# base_led_cube.net
KiCad netlist of a schematic drawn in Altium Designer
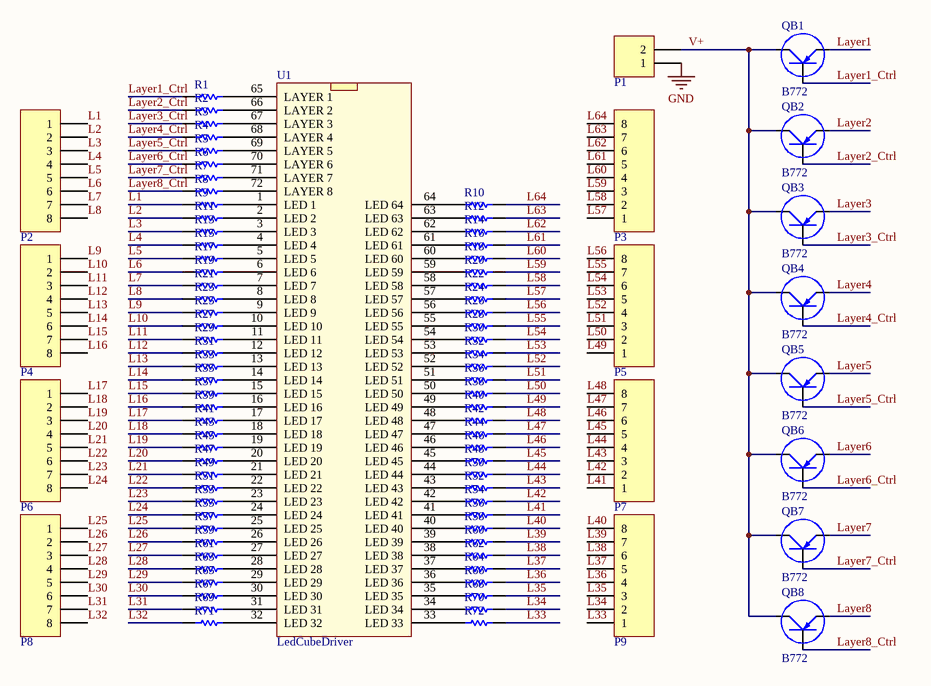
[diagram p0: base_led_cube.SchDoc]

(export (version "E")
  (design (tool "Eeschema 10.0.6"))
  (components
    (comp (ref "P1")
      (value "Domino 2")
      (footprint "DOMINO SMALL 2")
      (description "Domino, 2-Pin")
      (fields (field (name "PUBLISHER") "Altium Limited"))
      (libsource (lib "PIF_Library") (part "Domino 2"))
    )
    (comp (ref "P2")
      (value "Header 8")
      (footprint "JP8")
      (description "Header, 8-Pin")
      (fields (field (name "PUBLISHER") "Altium Limited"))
      (libsource (lib "") (part "Header 8_1"))
    )
    (comp (ref "P3")
      (value "Header 8")
      (footprint "JP8")
      (description "Header, 8-Pin")
      (fields (field (name "PUBLISHER") "Altium Limited"))
      (libsource (lib "PIF_Library") (part "Header 8"))
    )
    (comp (ref "P4")
      (value "Header 8")
      (footprint "JP8")
      (description "Header, 8-Pin")
      (fields (field (name "PUBLISHER") "Altium Limited"))
      (libsource (lib "") (part "Header 8_1"))
    )
    (comp (ref "P5")
      (value "Header 8")
      (footprint "JP8")
      (description "Header, 8-Pin")
      (fields (field (name "PUBLISHER") "Altium Limited"))
      (libsource (lib "PIF_Library") (part "Header 8"))
    )
    (comp (ref "P6")
      (value "Header 8")
      (footprint "JP8")
      (description "Header, 8-Pin")
      (fields (field (name "PUBLISHER") "Altium Limited"))
      (libsource (lib "") (part "Header 8_1"))
    )
    (comp (ref "P7")
      (value "Header 8")
      (footprint "JP8")
      (description "Header, 8-Pin")
      (fields (field (name "PUBLISHER") "Altium Limited"))
      (libsource (lib "PIF_Library") (part "Header 8"))
    )
    (comp (ref "P8")
      (value "Header 8")
      (footprint "JP8")
      (description "Header, 8-Pin")
      (fields (field (name "PUBLISHER") "Altium Limited"))
      (libsource (lib "") (part "Header 8_1"))
    )
    (comp (ref "P9")
      (value "Header 8")
      (footprint "JP8")
      (description "Header, 8-Pin")
      (fields (field (name "PUBLISHER") "Altium Limited"))
      (libsource (lib "PIF_Library") (part "Header 8"))
    )
    (comp (ref "QB1")
      (value "B772")
      (footprint "To-126")
      (description "PNP 30V - 3A")
      (libsource (lib "HN_Library") (part "2SB772"))
    )
    (comp (ref "QB2")
      (value "B772")
      (footprint "To-126")
      (description "PNP 30V - 3A")
      (libsource (lib "HN_Library") (part "2SB772"))
    )
    (comp (ref "QB3")
      (value "B772")
      (footprint "To-126")
      (description "PNP 30V - 3A")
      (libsource (lib "HN_Library") (part "2SB772"))
    )
    (comp (ref "QB4")
      (value "B772")
      (footprint "To-126")
      (description "PNP 30V - 3A")
      (libsource (lib "HN_Library") (part "2SB772"))
    )
    (comp (ref "QB5")
      (value "B772")
      (footprint "To-126")
      (description "PNP 30V - 3A")
      (libsource (lib "HN_Library") (part "2SB772"))
    )
    (comp (ref "QB6")
      (value "B772")
      (footprint "To-126")
      (description "PNP 30V - 3A")
      (libsource (lib "HN_Library") (part "2SB772"))
    )
    (comp (ref "QB7")
      (value "B772")
      (footprint "To-126")
      (description "PNP 30V - 3A")
      (libsource (lib "HN_Library") (part "2SB772"))
    )
    (comp (ref "QB8")
      (value "B772")
      (footprint "To-126")
      (description "PNP 30V - 3A")
      (libsource (lib "HN_Library") (part "2SB772"))
    )
    (comp (ref "R1")
      (value "RESISTOR SMD")
      (footprint "RES-SM-0805")
      (description "Resistor")
      (libsource (lib "PIF_Library") (part "RESISTOR SMD"))
    )
    (comp (ref "R2")
      (value "RESISTOR SMD")
      (footprint "RES-SM-0805")
      (description "Resistor")
      (libsource (lib "PIF_Library") (part "RESISTOR SMD"))
    )
    (comp (ref "R3")
      (value "RESISTOR SMD")
      (footprint "RES-SM-0805")
      (description "Resistor")
      (libsource (lib "PIF_Library") (part "RESISTOR SMD"))
    )
    (comp (ref "R4")
      (value "RESISTOR SMD")
      (footprint "RES-SM-0805")
      (description "Resistor")
      (libsource (lib "PIF_Library") (part "RESISTOR SMD"))
    )
    (comp (ref "R5")
      (value "RESISTOR SMD")
      (footprint "RES-SM-0805")
      (description "Resistor")
      (libsource (lib "PIF_Library") (part "RESISTOR SMD"))
    )
    (comp (ref "R6")
      (value "RESISTOR SMD")
      (footprint "RES-SM-0805")
      (description "Resistor")
      (libsource (lib "PIF_Library") (part "RESISTOR SMD"))
    )
    (comp (ref "R7")
      (value "RESISTOR SMD")
      (footprint "RES-SM-0805")
      (description "Resistor")
      (libsource (lib "PIF_Library") (part "RESISTOR SMD"))
    )
    (comp (ref "R8")
      (value "RESISTOR SMD")
      (footprint "RES-SM-0805")
      (description "Resistor")
      (libsource (lib "PIF_Library") (part "RESISTOR SMD"))
    )
    (comp (ref "R9")
      (value "RESISTOR SMD")
      (footprint "RES-SM-0805")
      (description "Resistor")
      (libsource (lib "PIF_Library") (part "RESISTOR SMD"))
    )
    (comp (ref "R10")
      (value "RESISTOR SMD")
      (footprint "RES-SM-0805")
      (description "Resistor")
      (libsource (lib "PIF_Library") (part "RESISTOR SMD"))
    )
    (comp (ref "R11")
      (value "RESISTOR SMD")
      (footprint "RES-SM-0805")
      (description "Resistor")
      (libsource (lib "PIF_Library") (part "RESISTOR SMD"))
    )
    (comp (ref "R12")
      (value "RESISTOR SMD")
      (footprint "RES-SM-0805")
      (description "Resistor")
      (libsource (lib "PIF_Library") (part "RESISTOR SMD"))
    )
    (comp (ref "R13")
      (value "RESISTOR SMD")
      (footprint "RES-SM-0805")
      (description "Resistor")
      (libsource (lib "PIF_Library") (part "RESISTOR SMD"))
    )
    (comp (ref "R14")
      (value "RESISTOR SMD")
      (footprint "RES-SM-0805")
      (description "Resistor")
      (libsource (lib "PIF_Library") (part "RESISTOR SMD"))
    )
    (comp (ref "R15")
      (value "RESISTOR SMD")
      (footprint "RES-SM-0805")
      (description "Resistor")
      (libsource (lib "PIF_Library") (part "RESISTOR SMD"))
    )
    (comp (ref "R16")
      (value "RESISTOR SMD")
      (footprint "RES-SM-0805")
      (description "Resistor")
      (libsource (lib "PIF_Library") (part "RESISTOR SMD"))
    )
    (comp (ref "R17")
      (value "RESISTOR SMD")
      (footprint "RES-SM-0805")
      (description "Resistor")
      (libsource (lib "PIF_Library") (part "RESISTOR SMD"))
    )
    (comp (ref "R18")
      (value "RESISTOR SMD")
      (footprint "RES-SM-0805")
      (description "Resistor")
      (libsource (lib "PIF_Library") (part "RESISTOR SMD"))
    )
    (comp (ref "R19")
      (value "RESISTOR SMD")
      (footprint "RES-SM-0805")
      (description "Resistor")
      (libsource (lib "PIF_Library") (part "RESISTOR SMD"))
    )
    (comp (ref "R20")
      (value "RESISTOR SMD")
      (footprint "RES-SM-0805")
      (description "Resistor")
      (libsource (lib "PIF_Library") (part "RESISTOR SMD"))
    )
    (comp (ref "R21")
      (value "RESISTOR SMD")
      (footprint "RES-SM-0805")
      (description "Resistor")
      (libsource (lib "PIF_Library") (part "RESISTOR SMD"))
    )
    (comp (ref "R22")
      (value "RESISTOR SMD")
      (footprint "RES-SM-0805")
      (description "Resistor")
      (libsource (lib "PIF_Library") (part "RESISTOR SMD"))
    )
    (comp (ref "R23")
      (value "RESISTOR SMD")
      (footprint "RES-SM-0805")
      (description "Resistor")
      (libsource (lib "PIF_Library") (part "RESISTOR SMD"))
    )
    (comp (ref "R24")
      (value "RESISTOR SMD")
      (footprint "RES-SM-0805")
      (description "Resistor")
      (libsource (lib "PIF_Library") (part "RESISTOR SMD"))
    )
    (comp (ref "R25")
      (value "RESISTOR SMD")
      (footprint "RES-SM-0805")
      (description "Resistor")
      (libsource (lib "PIF_Library") (part "RESISTOR SMD"))
    )
    (comp (ref "R26")
      (value "RESISTOR SMD")
      (footprint "RES-SM-0805")
      (description "Resistor")
      (libsource (lib "PIF_Library") (part "RESISTOR SMD"))
    )
    (comp (ref "R27")
      (value "RESISTOR SMD")
      (footprint "RES-SM-0805")
      (description "Resistor")
      (libsource (lib "PIF_Library") (part "RESISTOR SMD"))
    )
    (comp (ref "R28")
      (value "RESISTOR SMD")
      (footprint "RES-SM-0805")
      (description "Resistor")
      (libsource (lib "PIF_Library") (part "RESISTOR SMD"))
    )
    (comp (ref "R29")
      (value "RESISTOR SMD")
      (footprint "RES-SM-0805")
      (description "Resistor")
      (libsource (lib "PIF_Library") (part "RESISTOR SMD"))
    )
    (comp (ref "R30")
      (value "RESISTOR SMD")
      (footprint "RES-SM-0805")
      (description "Resistor")
      (libsource (lib "PIF_Library") (part "RESISTOR SMD"))
    )
    (comp (ref "R31")
      (value "RESISTOR SMD")
      (footprint "RES-SM-0805")
      (description "Resistor")
      (libsource (lib "PIF_Library") (part "RESISTOR SMD"))
    )
    (comp (ref "R32")
      (value "RESISTOR SMD")
      (footprint "RES-SM-0805")
      (description "Resistor")
      (libsource (lib "PIF_Library") (part "RESISTOR SMD"))
    )
    (comp (ref "R33")
      (value "RESISTOR SMD")
      (footprint "RES-SM-0805")
      (description "Resistor")
      (libsource (lib "PIF_Library") (part "RESISTOR SMD"))
    )
    (comp (ref "R34")
      (value "RESISTOR SMD")
      (footprint "RES-SM-0805")
      (description "Resistor")
      (libsource (lib "PIF_Library") (part "RESISTOR SMD"))
    )
    (comp (ref "R35")
      (value "RESISTOR SMD")
      (footprint "RES-SM-0805")
      (description "Resistor")
      (libsource (lib "PIF_Library") (part "RESISTOR SMD"))
    )
    (comp (ref "R36")
      (value "RESISTOR SMD")
      (footprint "RES-SM-0805")
      (description "Resistor")
      (libsource (lib "PIF_Library") (part "RESISTOR SMD"))
    )
    (comp (ref "R37")
      (value "RESISTOR SMD")
      (footprint "RES-SM-0805")
      (description "Resistor")
      (libsource (lib "PIF_Library") (part "RESISTOR SMD"))
    )
    (comp (ref "R38")
      (value "RESISTOR SMD")
      (footprint "RES-SM-0805")
      (description "Resistor")
      (libsource (lib "PIF_Library") (part "RESISTOR SMD"))
    )
    (comp (ref "R39")
      (value "RESISTOR SMD")
      (footprint "RES-SM-0805")
      (description "Resistor")
      (libsource (lib "PIF_Library") (part "RESISTOR SMD"))
    )
    (comp (ref "R40")
      (value "RESISTOR SMD")
      (footprint "RES-SM-0805")
      (description "Resistor")
      (libsource (lib "PIF_Library") (part "RESISTOR SMD"))
    )
    (comp (ref "R41")
      (value "RESISTOR SMD")
      (footprint "RES-SM-0805")
      (description "Resistor")
      (libsource (lib "PIF_Library") (part "RESISTOR SMD"))
    )
    (comp (ref "R42")
      (value "RESISTOR SMD")
      (footprint "RES-SM-0805")
      (description "Resistor")
      (libsource (lib "PIF_Library") (part "RESISTOR SMD"))
    )
    (comp (ref "R43")
      (value "RESISTOR SMD")
      (footprint "RES-SM-0805")
      (description "Resistor")
      (libsource (lib "PIF_Library") (part "RESISTOR SMD"))
    )
    (comp (ref "R44")
      (value "RESISTOR SMD")
      (footprint "RES-SM-0805")
      (description "Resistor")
      (libsource (lib "PIF_Library") (part "RESISTOR SMD"))
    )
    (comp (ref "R45")
      (value "RESISTOR SMD")
      (footprint "RES-SM-0805")
      (description "Resistor")
      (libsource (lib "PIF_Library") (part "RESISTOR SMD"))
    )
    (comp (ref "R46")
      (value "RESISTOR SMD")
      (footprint "RES-SM-0805")
      (description "Resistor")
      (libsource (lib "PIF_Library") (part "RESISTOR SMD"))
    )
    (comp (ref "R47")
      (value "RESISTOR SMD")
      (footprint "RES-SM-0805")
      (description "Resistor")
      (libsource (lib "PIF_Library") (part "RESISTOR SMD"))
    )
    (comp (ref "R48")
      (value "RESISTOR SMD")
      (footprint "RES-SM-0805")
      (description "Resistor")
      (libsource (lib "PIF_Library") (part "RESISTOR SMD"))
    )
    (comp (ref "R49")
      (value "RESISTOR SMD")
      (footprint "RES-SM-0805")
      (description "Resistor")
      (libsource (lib "PIF_Library") (part "RESISTOR SMD"))
    )
    (comp (ref "R50")
      (value "RESISTOR SMD")
      (footprint "RES-SM-0805")
      (description "Resistor")
      (libsource (lib "PIF_Library") (part "RESISTOR SMD"))
    )
    (comp (ref "R51")
      (value "RESISTOR SMD")
      (footprint "RES-SM-0805")
      (description "Resistor")
      (libsource (lib "PIF_Library") (part "RESISTOR SMD"))
    )
    (comp (ref "R52")
      (value "RESISTOR SMD")
      (footprint "RES-SM-0805")
      (description "Resistor")
      (libsource (lib "PIF_Library") (part "RESISTOR SMD"))
    )
    (comp (ref "R53")
      (value "RESISTOR SMD")
      (footprint "RES-SM-0805")
      (description "Resistor")
      (libsource (lib "PIF_Library") (part "RESISTOR SMD"))
    )
    (comp (ref "R54")
      (value "RESISTOR SMD")
      (footprint "RES-SM-0805")
      (description "Resistor")
      (libsource (lib "PIF_Library") (part "RESISTOR SMD"))
    )
    (comp (ref "R55")
      (value "RESISTOR SMD")
      (footprint "RES-SM-0805")
      (description "Resistor")
      (libsource (lib "PIF_Library") (part "RESISTOR SMD"))
    )
    (comp (ref "R56")
      (value "RESISTOR SMD")
      (footprint "RES-SM-0805")
      (description "Resistor")
      (libsource (lib "PIF_Library") (part "RESISTOR SMD"))
    )
    (comp (ref "R57")
      (value "RESISTOR SMD")
      (footprint "RES-SM-0805")
      (description "Resistor")
      (libsource (lib "PIF_Library") (part "RESISTOR SMD"))
    )
    (comp (ref "R58")
      (value "RESISTOR SMD")
      (footprint "RES-SM-0805")
      (description "Resistor")
      (libsource (lib "PIF_Library") (part "RESISTOR SMD"))
    )
    (comp (ref "R59")
      (value "RESISTOR SMD")
      (footprint "RES-SM-0805")
      (description "Resistor")
      (libsource (lib "PIF_Library") (part "RESISTOR SMD"))
    )
    (comp (ref "R60")
      (value "RESISTOR SMD")
      (footprint "RES-SM-0805")
      (description "Resistor")
      (libsource (lib "PIF_Library") (part "RESISTOR SMD"))
    )
    (comp (ref "R61")
      (value "RESISTOR SMD")
      (footprint "RES-SM-0805")
      (description "Resistor")
      (libsource (lib "PIF_Library") (part "RESISTOR SMD"))
    )
    (comp (ref "R62")
      (value "RESISTOR SMD")
      (footprint "RES-SM-0805")
      (description "Resistor")
      (libsource (lib "PIF_Library") (part "RESISTOR SMD"))
    )
    (comp (ref "R63")
      (value "RESISTOR SMD")
      (footprint "RES-SM-0805")
      (description "Resistor")
      (libsource (lib "PIF_Library") (part "RESISTOR SMD"))
    )
    (comp (ref "R64")
      (value "RESISTOR SMD")
      (footprint "RES-SM-0805")
      (description "Resistor")
      (libsource (lib "PIF_Library") (part "RESISTOR SMD"))
    )
    (comp (ref "R65")
      (value "RESISTOR SMD")
      (footprint "RES-SM-0805")
      (description "Resistor")
      (libsource (lib "PIF_Library") (part "RESISTOR SMD"))
    )
    (comp (ref "R66")
      (value "RESISTOR SMD")
      (footprint "RES-SM-0805")
      (description "Resistor")
      (libsource (lib "PIF_Library") (part "RESISTOR SMD"))
    )
    (comp (ref "R67")
      (value "RESISTOR SMD")
      (footprint "RES-SM-0805")
      (description "Resistor")
      (libsource (lib "PIF_Library") (part "RESISTOR SMD"))
    )
    (comp (ref "R68")
      (value "RESISTOR SMD")
      (footprint "RES-SM-0805")
      (description "Resistor")
      (libsource (lib "PIF_Library") (part "RESISTOR SMD"))
    )
    (comp (ref "R69")
      (value "RESISTOR SMD")
      (footprint "RES-SM-0805")
      (description "Resistor")
      (libsource (lib "PIF_Library") (part "RESISTOR SMD"))
    )
    (comp (ref "R70")
      (value "RESISTOR SMD")
      (footprint "RES-SM-0805")
      (description "Resistor")
      (libsource (lib "PIF_Library") (part "RESISTOR SMD"))
    )
    (comp (ref "R71")
      (value "RESISTOR SMD")
      (footprint "RES-SM-0805")
      (description "Resistor")
      (libsource (lib "PIF_Library") (part "RESISTOR SMD"))
    )
    (comp (ref "R72")
      (value "RESISTOR SMD")
      (footprint "RES-SM-0805")
      (description "Resistor")
      (libsource (lib "PIF_Library") (part "RESISTOR SMD"))
    )
    (comp (ref "U1")
      (value "LedCubeDriver")
      (footprint "LED CUBE Driver")
      (libsource (lib "HN_Library") (part "LED Cube Driver"))
    )
  )
  (nets
    (net (code "1") (name "/L1") (class "Default")
      (node (ref "P2") (pin "1") (pinfunction "1_1") (pintype "passive"))
      (node (ref "R9") (pin "1") (pinfunction "1_1") (pintype "passive"))
    )
    (net (code "2") (name "/L2") (class "Default")
      (node (ref "P2") (pin "2") (pinfunction "2_2") (pintype "passive"))
      (node (ref "R11") (pin "1") (pinfunction "1_1") (pintype "passive"))
    )
    (net (code "3") (name "/L3") (class "Default")
      (node (ref "P2") (pin "3") (pinfunction "3_3") (pintype "passive"))
      (node (ref "R13") (pin "1") (pinfunction "1_1") (pintype "passive"))
    )
    (net (code "4") (name "/L4") (class "Default")
      (node (ref "P2") (pin "4") (pinfunction "4_4") (pintype "passive"))
      (node (ref "R15") (pin "1") (pinfunction "1_1") (pintype "passive"))
    )
    (net (code "5") (name "/L5") (class "Default")
      (node (ref "P2") (pin "5") (pinfunction "5_5") (pintype "passive"))
      (node (ref "R17") (pin "1") (pinfunction "1_1") (pintype "passive"))
    )
    (net (code "6") (name "/L6") (class "Default")
      (node (ref "P2") (pin "6") (pinfunction "6_6") (pintype "passive"))
      (node (ref "R19") (pin "1") (pinfunction "1_1") (pintype "passive"))
    )
    (net (code "7") (name "/L7") (class "Default")
      (node (ref "P2") (pin "7") (pinfunction "7_7") (pintype "passive"))
      (node (ref "R21") (pin "1") (pinfunction "1_1") (pintype "passive"))
    )
    (net (code "8") (name "/L8") (class "Default")
      (node (ref "P2") (pin "8") (pinfunction "8_8") (pintype "passive"))
      (node (ref "R23") (pin "1") (pinfunction "1_1") (pintype "passive"))
    )
    (net (code "9") (name "/L9") (class "Default")
      (node (ref "P4") (pin "1") (pinfunction "1_1") (pintype "passive"))
      (node (ref "R25") (pin "1") (pinfunction "1_1") (pintype "passive"))
    )
    (net (code "10") (name "/L10") (class "Default")
      (node (ref "P4") (pin "2") (pinfunction "2_2") (pintype "passive"))
      (node (ref "R27") (pin "1") (pinfunction "1_1") (pintype "passive"))
    )
    (net (code "11") (name "/L11") (class "Default")
      (node (ref "P4") (pin "3") (pinfunction "3_3") (pintype "passive"))
      (node (ref "R29") (pin "1") (pinfunction "1_1") (pintype "passive"))
    )
    (net (code "12") (name "/L12") (class "Default")
      (node (ref "P4") (pin "4") (pinfunction "4_4") (pintype "passive"))
      (node (ref "R31") (pin "1") (pinfunction "1_1") (pintype "passive"))
    )
    (net (code "13") (name "/L13") (class "Default")
      (node (ref "P4") (pin "5") (pinfunction "5_5") (pintype "passive"))
      (node (ref "R33") (pin "1") (pinfunction "1_1") (pintype "passive"))
    )
    (net (code "14") (name "/L14") (class "Default")
      (node (ref "P4") (pin "6") (pinfunction "6_6") (pintype "passive"))
      (node (ref "R35") (pin "1") (pinfunction "1_1") (pintype "passive"))
    )
    (net (code "15") (name "/L15") (class "Default")
      (node (ref "P4") (pin "7") (pinfunction "7_7") (pintype "passive"))
      (node (ref "R37") (pin "1") (pinfunction "1_1") (pintype "passive"))
    )
    (net (code "16") (name "/L16") (class "Default")
      (node (ref "P4") (pin "8") (pinfunction "8_8") (pintype "passive"))
      (node (ref "R39") (pin "1") (pinfunction "1_1") (pintype "passive"))
    )
    (net (code "17") (name "/L17") (class "Default")
      (node (ref "P6") (pin "1") (pinfunction "1_1") (pintype "passive"))
      (node (ref "R41") (pin "1") (pinfunction "1_1") (pintype "passive"))
    )
    (net (code "18") (name "/L18") (class "Default")
      (node (ref "P6") (pin "2") (pinfunction "2_2") (pintype "passive"))
      (node (ref "R43") (pin "1") (pinfunction "1_1") (pintype "passive"))
    )
    (net (code "19") (name "/L19") (class "Default")
      (node (ref "P6") (pin "3") (pinfunction "3_3") (pintype "passive"))
      (node (ref "R45") (pin "1") (pinfunction "1_1") (pintype "passive"))
    )
    (net (code "20") (name "/L20") (class "Default")
      (node (ref "P6") (pin "4") (pinfunction "4_4") (pintype "passive"))
      (node (ref "R47") (pin "1") (pinfunction "1_1") (pintype "passive"))
    )
    (net (code "21") (name "/L21") (class "Default")
      (node (ref "P6") (pin "5") (pinfunction "5_5") (pintype "passive"))
      (node (ref "R49") (pin "1") (pinfunction "1_1") (pintype "passive"))
    )
    (net (code "22") (name "/L22") (class "Default")
      (node (ref "P6") (pin "6") (pinfunction "6_6") (pintype "passive"))
      (node (ref "R51") (pin "1") (pinfunction "1_1") (pintype "passive"))
    )
    (net (code "23") (name "/L23") (class "Default")
      (node (ref "P6") (pin "7") (pinfunction "7_7") (pintype "passive"))
      (node (ref "R53") (pin "1") (pinfunction "1_1") (pintype "passive"))
    )
    (net (code "24") (name "/L24") (class "Default")
      (node (ref "P6") (pin "8") (pinfunction "8_8") (pintype "passive"))
      (node (ref "R55") (pin "1") (pinfunction "1_1") (pintype "passive"))
    )
    (net (code "25") (name "/L25") (class "Default")
      (node (ref "P8") (pin "1") (pinfunction "1_1") (pintype "passive"))
      (node (ref "R57") (pin "1") (pinfunction "1_1") (pintype "passive"))
    )
    (net (code "26") (name "/L26") (class "Default")
      (node (ref "P8") (pin "2") (pinfunction "2_2") (pintype "passive"))
      (node (ref "R59") (pin "1") (pinfunction "1_1") (pintype "passive"))
    )
    (net (code "27") (name "/L27") (class "Default")
      (node (ref "P8") (pin "3") (pinfunction "3_3") (pintype "passive"))
      (node (ref "R61") (pin "1") (pinfunction "1_1") (pintype "passive"))
    )
    (net (code "28") (name "/L28") (class "Default")
      (node (ref "P8") (pin "4") (pinfunction "4_4") (pintype "passive"))
      (node (ref "R63") (pin "1") (pinfunction "1_1") (pintype "passive"))
    )
    (net (code "29") (name "/L29") (class "Default")
      (node (ref "P8") (pin "5") (pinfunction "5_5") (pintype "passive"))
      (node (ref "R65") (pin "1") (pinfunction "1_1") (pintype "passive"))
    )
    (net (code "30") (name "/L30") (class "Default")
      (node (ref "P8") (pin "6") (pinfunction "6_6") (pintype "passive"))
      (node (ref "R67") (pin "1") (pinfunction "1_1") (pintype "passive"))
    )
    (net (code "31") (name "/L31") (class "Default")
      (node (ref "P8") (pin "7") (pinfunction "7_7") (pintype "passive"))
      (node (ref "R69") (pin "1") (pinfunction "1_1") (pintype "passive"))
    )
    (net (code "32") (name "/L32") (class "Default")
      (node (ref "P8") (pin "8") (pinfunction "8_8") (pintype "passive"))
      (node (ref "R71") (pin "1") (pinfunction "1_1") (pintype "passive"))
    )
    (net (code "33") (name "/L33") (class "Default")
      (node (ref "P9") (pin "1") (pinfunction "1_1") (pintype "passive"))
      (node (ref "R72") (pin "1") (pinfunction "1_1") (pintype "passive"))
    )
    (net (code "34") (name "/L34") (class "Default")
      (node (ref "P9") (pin "2") (pinfunction "2_2") (pintype "passive"))
      (node (ref "R70") (pin "1") (pinfunction "1_1") (pintype "passive"))
    )
    (net (code "35") (name "/L35") (class "Default")
      (node (ref "P9") (pin "3") (pinfunction "3_3") (pintype "passive"))
      (node (ref "R68") (pin "1") (pinfunction "1_1") (pintype "passive"))
    )
    (net (code "36") (name "/L36") (class "Default")
      (node (ref "P9") (pin "4") (pinfunction "4_4") (pintype "passive"))
      (node (ref "R66") (pin "1") (pinfunction "1_1") (pintype "passive"))
    )
    (net (code "37") (name "/L37") (class "Default")
      (node (ref "P9") (pin "5") (pinfunction "5_5") (pintype "passive"))
      (node (ref "R64") (pin "1") (pinfunction "1_1") (pintype "passive"))
    )
    (net (code "38") (name "/L38") (class "Default")
      (node (ref "P9") (pin "6") (pinfunction "6_6") (pintype "passive"))
      (node (ref "R62") (pin "1") (pinfunction "1_1") (pintype "passive"))
    )
    (net (code "39") (name "/L39") (class "Default")
      (node (ref "P9") (pin "7") (pinfunction "7_7") (pintype "passive"))
      (node (ref "R60") (pin "1") (pinfunction "1_1") (pintype "passive"))
    )
    (net (code "40") (name "/L40") (class "Default")
      (node (ref "P9") (pin "8") (pinfunction "8_8") (pintype "passive"))
      (node (ref "R58") (pin "1") (pinfunction "1_1") (pintype "passive"))
    )
    (net (code "41") (name "/L41") (class "Default")
      (node (ref "P7") (pin "1") (pinfunction "1_1") (pintype "passive"))
      (node (ref "R56") (pin "1") (pinfunction "1_1") (pintype "passive"))
    )
    (net (code "42") (name "/L42") (class "Default")
      (node (ref "P7") (pin "2") (pinfunction "2_2") (pintype "passive"))
      (node (ref "R54") (pin "1") (pinfunction "1_1") (pintype "passive"))
    )
    (net (code "43") (name "/L43") (class "Default")
      (node (ref "P7") (pin "3") (pinfunction "3_3") (pintype "passive"))
      (node (ref "R52") (pin "1") (pinfunction "1_1") (pintype "passive"))
    )
    (net (code "44") (name "/L44") (class "Default")
      (node (ref "P7") (pin "4") (pinfunction "4_4") (pintype "passive"))
      (node (ref "R50") (pin "1") (pinfunction "1_1") (pintype "passive"))
    )
    (net (code "45") (name "/L45") (class "Default")
      (node (ref "P7") (pin "5") (pinfunction "5_5") (pintype "passive"))
      (node (ref "R48") (pin "1") (pinfunction "1_1") (pintype "passive"))
    )
    (net (code "46") (name "/L46") (class "Default")
      (node (ref "P7") (pin "6") (pinfunction "6_6") (pintype "passive"))
      (node (ref "R46") (pin "1") (pinfunction "1_1") (pintype "passive"))
    )
    (net (code "47") (name "/L47") (class "Default")
      (node (ref "P7") (pin "7") (pinfunction "7_7") (pintype "passive"))
      (node (ref "R44") (pin "1") (pinfunction "1_1") (pintype "passive"))
    )
    (net (code "48") (name "/L48") (class "Default")
      (node (ref "P7") (pin "8") (pinfunction "8_8") (pintype "passive"))
      (node (ref "R42") (pin "1") (pinfunction "1_1") (pintype "passive"))
    )
    (net (code "49") (name "/L49") (class "Default")
      (node (ref "P5") (pin "1") (pinfunction "1_1") (pintype "passive"))
      (node (ref "R40") (pin "1") (pinfunction "1_1") (pintype "passive"))
    )
    (net (code "50") (name "/L50") (class "Default")
      (node (ref "P5") (pin "2") (pinfunction "2_2") (pintype "passive"))
      (node (ref "R38") (pin "1") (pinfunction "1_1") (pintype "passive"))
    )
    (net (code "51") (name "/L51") (class "Default")
      (node (ref "P5") (pin "3") (pinfunction "3_3") (pintype "passive"))
      (node (ref "R36") (pin "1") (pinfunction "1_1") (pintype "passive"))
    )
    (net (code "52") (name "/L52") (class "Default")
      (node (ref "P5") (pin "4") (pinfunction "4_4") (pintype "passive"))
      (node (ref "R34") (pin "1") (pinfunction "1_1") (pintype "passive"))
    )
    (net (code "53") (name "/L53") (class "Default")
      (node (ref "P5") (pin "5") (pinfunction "5_5") (pintype "passive"))
      (node (ref "R32") (pin "1") (pinfunction "1_1") (pintype "passive"))
    )
    (net (code "54") (name "/L54") (class "Default")
      (node (ref "P5") (pin "6") (pinfunction "6_6") (pintype "passive"))
      (node (ref "R30") (pin "1") (pinfunction "1_1") (pintype "passive"))
    )
    (net (code "55") (name "/L55") (class "Default")
      (node (ref "P5") (pin "7") (pinfunction "7_7") (pintype "passive"))
      (node (ref "R28") (pin "1") (pinfunction "1_1") (pintype "passive"))
    )
    (net (code "56") (name "/L56") (class "Default")
      (node (ref "P5") (pin "8") (pinfunction "8_8") (pintype "passive"))
      (node (ref "R26") (pin "1") (pinfunction "1_1") (pintype "passive"))
    )
    (net (code "57") (name "/L57") (class "Default")
      (node (ref "P3") (pin "1") (pinfunction "1_1") (pintype "passive"))
      (node (ref "R24") (pin "1") (pinfunction "1_1") (pintype "passive"))
    )
    (net (code "58") (name "/L58") (class "Default")
      (node (ref "P3") (pin "2") (pinfunction "2_2") (pintype "passive"))
      (node (ref "R22") (pin "1") (pinfunction "1_1") (pintype "passive"))
    )
    (net (code "59") (name "/L59") (class "Default")
      (node (ref "P3") (pin "3") (pinfunction "3_3") (pintype "passive"))
      (node (ref "R20") (pin "1") (pinfunction "1_1") (pintype "passive"))
    )
    (net (code "60") (name "/L60") (class "Default")
      (node (ref "P3") (pin "4") (pinfunction "4_4") (pintype "passive"))
      (node (ref "R18") (pin "1") (pinfunction "1_1") (pintype "passive"))
    )
    (net (code "61") (name "/L61") (class "Default")
      (node (ref "P3") (pin "5") (pinfunction "5_5") (pintype "passive"))
      (node (ref "R16") (pin "1") (pinfunction "1_1") (pintype "passive"))
    )
    (net (code "62") (name "/L62") (class "Default")
      (node (ref "P3") (pin "6") (pinfunction "6_6") (pintype "passive"))
      (node (ref "R14") (pin "1") (pinfunction "1_1") (pintype "passive"))
    )
    (net (code "63") (name "/L63") (class "Default")
      (node (ref "P3") (pin "7") (pinfunction "7_7") (pintype "passive"))
      (node (ref "R12") (pin "1") (pinfunction "1_1") (pintype "passive"))
    )
    (net (code "64") (name "/L64") (class "Default")
      (node (ref "P3") (pin "8") (pinfunction "8_8") (pintype "passive"))
      (node (ref "R10") (pin "1") (pinfunction "1_1") (pintype "passive"))
    )
    (net (code "65") (name "/Layer1") (class "Default")
      (node (ref "QB1") (pin "3") (pinfunction "E_3") (pintype "passive"))
    )
    (net (code "66") (name "/Layer1_Ctrl") (class "Default")
      (node (ref "QB1") (pin "1") (pinfunction "B_1") (pintype "passive"))
      (node (ref "R1") (pin "1") (pinfunction "1_1") (pintype "passive"))
    )
    (net (code "67") (name "/Layer2") (class "Default")
      (node (ref "QB2") (pin "3") (pinfunction "E_3") (pintype "passive"))
    )
    (net (code "68") (name "/Layer2_Ctrl") (class "Default")
      (node (ref "QB2") (pin "1") (pinfunction "B_1") (pintype "passive"))
      (node (ref "R2") (pin "1") (pinfunction "1_1") (pintype "passive"))
    )
    (net (code "69") (name "/Layer3") (class "Default")
      (node (ref "QB3") (pin "3") (pinfunction "E_3") (pintype "passive"))
    )
    (net (code "70") (name "/Layer3_Ctrl") (class "Default")
      (node (ref "QB3") (pin "1") (pinfunction "B_1") (pintype "passive"))
      (node (ref "R3") (pin "1") (pinfunction "1_1") (pintype "passive"))
    )
    (net (code "71") (name "/Layer4") (class "Default")
      (node (ref "QB4") (pin "3") (pinfunction "E_3") (pintype "passive"))
    )
    (net (code "72") (name "/Layer4_Ctrl") (class "Default")
      (node (ref "QB4") (pin "1") (pinfunction "B_1") (pintype "passive"))
      (node (ref "R4") (pin "1") (pinfunction "1_1") (pintype "passive"))
    )
    (net (code "73") (name "/Layer5") (class "Default")
      (node (ref "QB5") (pin "3") (pinfunction "E_3") (pintype "passive"))
    )
    (net (code "74") (name "/Layer5_Ctrl") (class "Default")
      (node (ref "QB5") (pin "1") (pinfunction "B_1") (pintype "passive"))
      (node (ref "R5") (pin "1") (pinfunction "1_1") (pintype "passive"))
    )
    (net (code "75") (name "/Layer6") (class "Default")
      (node (ref "QB6") (pin "3") (pinfunction "E_3") (pintype "passive"))
    )
    (net (code "76") (name "/Layer6_Ctrl") (class "Default")
      (node (ref "QB6") (pin "1") (pinfunction "B_1") (pintype "passive"))
      (node (ref "R6") (pin "1") (pinfunction "1_1") (pintype "passive"))
    )
    (net (code "77") (name "/Layer7") (class "Default")
      (node (ref "QB7") (pin "3") (pinfunction "E_3") (pintype "passive"))
    )
    (net (code "78") (name "/Layer7_Ctrl") (class "Default")
      (node (ref "QB7") (pin "1") (pinfunction "B_1") (pintype "passive"))
      (node (ref "R7") (pin "1") (pinfunction "1_1") (pintype "passive"))
    )
    (net (code "79") (name "/Layer8") (class "Default")
      (node (ref "QB8") (pin "3") (pinfunction "E_3") (pintype "passive"))
    )
    (net (code "80") (name "/Layer8_Ctrl") (class "Default")
      (node (ref "QB8") (pin "1") (pinfunction "B_1") (pintype "passive"))
      (node (ref "R8") (pin "1") (pinfunction "1_1") (pintype "passive"))
    )
    (net (code "81") (name "/V+") (class "Default")
      (node (ref "P1") (pin "2") (pinfunction "2_2") (pintype "passive"))
      (node (ref "QB1") (pin "2") (pinfunction "C_2") (pintype "passive"))
      (node (ref "QB2") (pin "2") (pinfunction "C_2") (pintype "passive"))
      (node (ref "QB3") (pin "2") (pinfunction "C_2") (pintype "passive"))
      (node (ref "QB4") (pin "2") (pinfunction "C_2") (pintype "passive"))
      (node (ref "QB5") (pin "2") (pinfunction "C_2") (pintype "passive"))
      (node (ref "QB6") (pin "2") (pinfunction "C_2") (pintype "passive"))
      (node (ref "QB7") (pin "2") (pinfunction "C_2") (pintype "passive"))
      (node (ref "QB8") (pin "2") (pinfunction "C_2") (pintype "passive"))
    )
    (net (code "82") (name "GND") (class "Default")
      (node (ref "P1") (pin "1") (pinfunction "1_1") (pintype "passive"))
    )
    (net (code "83") (name "Net-(U1-LAYER_1)") (class "Default")
      (node (ref "R1") (pin "2") (pinfunction "2_2") (pintype "passive"))
      (node (ref "U1") (pin "65") (pinfunction "LAYER_1_65") (pintype "passive"))
    )
    (net (code "84") (name "Net-(U1-LAYER_2)") (class "Default")
      (node (ref "R2") (pin "2") (pinfunction "2_2") (pintype "passive"))
      (node (ref "U1") (pin "66") (pinfunction "LAYER_2_66") (pintype "passive"))
    )
    (net (code "85") (name "Net-(U1-LAYER_3)") (class "Default")
      (node (ref "R3") (pin "2") (pinfunction "2_2") (pintype "passive"))
      (node (ref "U1") (pin "67") (pinfunction "LAYER_3_67") (pintype "passive"))
    )
    (net (code "86") (name "Net-(U1-LAYER_4)") (class "Default")
      (node (ref "R4") (pin "2") (pinfunction "2_2") (pintype "passive"))
      (node (ref "U1") (pin "68") (pinfunction "LAYER_4_68") (pintype "passive"))
    )
    (net (code "87") (name "Net-(U1-LAYER_5)") (class "Default")
      (node (ref "R5") (pin "2") (pinfunction "2_2") (pintype "passive"))
      (node (ref "U1") (pin "69") (pinfunction "LAYER_5_69") (pintype "passive"))
    )
    (net (code "88") (name "Net-(U1-LAYER_6)") (class "Default")
      (node (ref "R6") (pin "2") (pinfunction "2_2") (pintype "passive"))
      (node (ref "U1") (pin "70") (pinfunction "LAYER_6_70") (pintype "passive"))
    )
    (net (code "89") (name "Net-(U1-LAYER_7)") (class "Default")
      (node (ref "R7") (pin "2") (pinfunction "2_2") (pintype "passive"))
      (node (ref "U1") (pin "71") (pinfunction "LAYER_7_71") (pintype "passive"))
    )
    (net (code "90") (name "Net-(U1-LAYER_8)") (class "Default")
      (node (ref "R8") (pin "2") (pinfunction "2_2") (pintype "passive"))
      (node (ref "U1") (pin "72") (pinfunction "LAYER_8_72") (pintype "passive"))
    )
    (net (code "91") (name "Net-(U1-LED_1)") (class "Default")
      (node (ref "R9") (pin "2") (pinfunction "2_2") (pintype "passive"))
      (node (ref "U1") (pin "1") (pinfunction "LED_1_1") (pintype "passive"))
    )
    (net (code "92") (name "Net-(U1-LED_2)") (class "Default")
      (node (ref "R11") (pin "2") (pinfunction "2_2") (pintype "passive"))
      (node (ref "U1") (pin "2") (pinfunction "LED_2_2") (pintype "passive"))
    )
    (net (code "93") (name "Net-(U1-LED_3)") (class "Default")
      (node (ref "R13") (pin "2") (pinfunction "2_2") (pintype "passive"))
      (node (ref "U1") (pin "3") (pinfunction "LED_3_3") (pintype "passive"))
    )
    (net (code "94") (name "Net-(U1-LED_4)") (class "Default")
      (node (ref "R15") (pin "2") (pinfunction "2_2") (pintype "passive"))
      (node (ref "U1") (pin "4") (pinfunction "LED_4_4") (pintype "passive"))
    )
    (net (code "95") (name "Net-(U1-LED_5)") (class "Default")
      (node (ref "R17") (pin "2") (pinfunction "2_2") (pintype "passive"))
      (node (ref "U1") (pin "5") (pinfunction "LED_5_5") (pintype "passive"))
    )
    (net (code "96") (name "Net-(U1-LED_6)") (class "Default")
      (node (ref "R19") (pin "2") (pinfunction "2_2") (pintype "passive"))
      (node (ref "U1") (pin "6") (pinfunction "LED_6_6") (pintype "passive"))
    )
    (net (code "97") (name "Net-(U1-LED_7)") (class "Default")
      (node (ref "R21") (pin "2") (pinfunction "2_2") (pintype "passive"))
      (node (ref "U1") (pin "7") (pinfunction "LED_7_7") (pintype "passive"))
    )
    (net (code "98") (name "Net-(U1-LED_8)") (class "Default")
      (node (ref "R23") (pin "2") (pinfunction "2_2") (pintype "passive"))
      (node (ref "U1") (pin "8") (pinfunction "LED_8_8") (pintype "passive"))
    )
    (net (code "99") (name "Net-(U1-LED_9)") (class "Default")
      (node (ref "R25") (pin "2") (pinfunction "2_2") (pintype "passive"))
      (node (ref "U1") (pin "9") (pinfunction "LED_9_9") (pintype "passive"))
    )
    (net (code "100") (name "Net-(U1-LED_10)") (class "Default")
      (node (ref "R27") (pin "2") (pinfunction "2_2") (pintype "passive"))
      (node (ref "U1") (pin "10") (pinfunction "LED_10_10") (pintype "passive"))
    )
    (net (code "101") (name "Net-(U1-LED_11)") (class "Default")
      (node (ref "R29") (pin "2") (pinfunction "2_2") (pintype "passive"))
      (node (ref "U1") (pin "11") (pinfunction "LED_11_11") (pintype "passive"))
    )
    (net (code "102") (name "Net-(U1-LED_12)") (class "Default")
      (node (ref "R31") (pin "2") (pinfunction "2_2") (pintype "passive"))
      (node (ref "U1") (pin "12") (pinfunction "LED_12_12") (pintype "passive"))
    )
    (net (code "103") (name "Net-(U1-LED_13)") (class "Default")
      (node (ref "R33") (pin "2") (pinfunction "2_2") (pintype "passive"))
      (node (ref "U1") (pin "13") (pinfunction "LED_13_13") (pintype "passive"))
    )
    (net (code "104") (name "Net-(U1-LED_14)") (class "Default")
      (node (ref "R35") (pin "2") (pinfunction "2_2") (pintype "passive"))
      (node (ref "U1") (pin "14") (pinfunction "LED_14_14") (pintype "passive"))
    )
    (net (code "105") (name "Net-(U1-LED_15)") (class "Default")
      (node (ref "R37") (pin "2") (pinfunction "2_2") (pintype "passive"))
      (node (ref "U1") (pin "15") (pinfunction "LED_15_15") (pintype "passive"))
    )
    (net (code "106") (name "Net-(U1-LED_16)") (class "Default")
      (node (ref "R39") (pin "2") (pinfunction "2_2") (pintype "passive"))
      (node (ref "U1") (pin "16") (pinfunction "LED_16_16") (pintype "passive"))
    )
    (net (code "107") (name "Net-(U1-LED_17)") (class "Default")
      (node (ref "R41") (pin "2") (pinfunction "2_2") (pintype "passive"))
      (node (ref "U1") (pin "17") (pinfunction "LED_17_17") (pintype "passive"))
    )
    (net (code "108") (name "Net-(U1-LED_18)") (class "Default")
      (node (ref "R43") (pin "2") (pinfunction "2_2") (pintype "passive"))
      (node (ref "U1") (pin "18") (pinfunction "LED_18_18") (pintype "passive"))
    )
    (net (code "109") (name "Net-(U1-LED_19)") (class "Default")
      (node (ref "R45") (pin "2") (pinfunction "2_2") (pintype "passive"))
      (node (ref "U1") (pin "19") (pinfunction "LED_19_19") (pintype "passive"))
    )
    (net (code "110") (name "Net-(U1-LED_20)") (class "Default")
      (node (ref "R47") (pin "2") (pinfunction "2_2") (pintype "passive"))
      (node (ref "U1") (pin "20") (pinfunction "LED_20_20") (pintype "passive"))
    )
    (net (code "111") (name "Net-(U1-LED_21)") (class "Default")
      (node (ref "R49") (pin "2") (pinfunction "2_2") (pintype "passive"))
      (node (ref "U1") (pin "21") (pinfunction "LED_21_21") (pintype "passive"))
    )
    (net (code "112") (name "Net-(U1-LED_22)") (class "Default")
      (node (ref "R51") (pin "2") (pinfunction "2_2") (pintype "passive"))
      (node (ref "U1") (pin "22") (pinfunction "LED_22_22") (pintype "passive"))
    )
    (net (code "113") (name "Net-(U1-LED_23)") (class "Default")
      (node (ref "R53") (pin "2") (pinfunction "2_2") (pintype "passive"))
      (node (ref "U1") (pin "23") (pinfunction "LED_23_23") (pintype "passive"))
    )
    (net (code "114") (name "Net-(U1-LED_24)") (class "Default")
      (node (ref "R55") (pin "2") (pinfunction "2_2") (pintype "passive"))
      (node (ref "U1") (pin "24") (pinfunction "LED_24_24") (pintype "passive"))
    )
    (net (code "115") (name "Net-(U1-LED_25)") (class "Default")
      (node (ref "R57") (pin "2") (pinfunction "2_2") (pintype "passive"))
      (node (ref "U1") (pin "25") (pinfunction "LED_25_25") (pintype "passive"))
    )
    (net (code "116") (name "Net-(U1-LED_26)") (class "Default")
      (node (ref "R59") (pin "2") (pinfunction "2_2") (pintype "passive"))
      (node (ref "U1") (pin "26") (pinfunction "LED_26_26") (pintype "passive"))
    )
    (net (code "117") (name "Net-(U1-LED_27)") (class "Default")
      (node (ref "R61") (pin "2") (pinfunction "2_2") (pintype "passive"))
      (node (ref "U1") (pin "27") (pinfunction "LED_27_27") (pintype "passive"))
    )
    (net (code "118") (name "Net-(U1-LED_28)") (class "Default")
      (node (ref "R63") (pin "2") (pinfunction "2_2") (pintype "passive"))
      (node (ref "U1") (pin "28") (pinfunction "LED_28_28") (pintype "passive"))
    )
    (net (code "119") (name "Net-(U1-LED_29)") (class "Default")
      (node (ref "R65") (pin "2") (pinfunction "2_2") (pintype "passive"))
      (node (ref "U1") (pin "29") (pinfunction "LED_29_29") (pintype "passive"))
    )
    (net (code "120") (name "Net-(U1-LED_30)") (class "Default")
      (node (ref "R67") (pin "2") (pinfunction "2_2") (pintype "passive"))
      (node (ref "U1") (pin "30") (pinfunction "LED_30_30") (pintype "passive"))
    )
    (net (code "121") (name "Net-(U1-LED_31)") (class "Default")
      (node (ref "R69") (pin "2") (pinfunction "2_2") (pintype "passive"))
      (node (ref "U1") (pin "31") (pinfunction "LED_31_31") (pintype "passive"))
    )
    (net (code "122") (name "Net-(U1-LED_32)") (class "Default")
      (node (ref "R71") (pin "2") (pinfunction "2_2") (pintype "passive"))
      (node (ref "U1") (pin "32") (pinfunction "LED_32_32") (pintype "passive"))
    )
    (net (code "123") (name "Net-(U1-LED_33)") (class "Default")
      (node (ref "R72") (pin "2") (pinfunction "2_2") (pintype "passive"))
      (node (ref "U1") (pin "33") (pinfunction "LED_33_33") (pintype "passive"))
    )
    (net (code "124") (name "Net-(U1-LED_34)") (class "Default")
      (node (ref "R70") (pin "2") (pinfunction "2_2") (pintype "passive"))
      (node (ref "U1") (pin "34") (pinfunction "LED_34_34") (pintype "passive"))
    )
    (net (code "125") (name "Net-(U1-LED_35)") (class "Default")
      (node (ref "R68") (pin "2") (pinfunction "2_2") (pintype "passive"))
      (node (ref "U1") (pin "35") (pinfunction "LED_35_35") (pintype "passive"))
    )
    (net (code "126") (name "Net-(U1-LED_36)") (class "Default")
      (node (ref "R66") (pin "2") (pinfunction "2_2") (pintype "passive"))
      (node (ref "U1") (pin "36") (pinfunction "LED_36_36") (pintype "passive"))
    )
    (net (code "127") (name "Net-(U1-LED_37)") (class "Default")
      (node (ref "R64") (pin "2") (pinfunction "2_2") (pintype "passive"))
      (node (ref "U1") (pin "37") (pinfunction "LED_37_37") (pintype "passive"))
    )
    (net (code "128") (name "Net-(U1-LED_38)") (class "Default")
      (node (ref "R62") (pin "2") (pinfunction "2_2") (pintype "passive"))
      (node (ref "U1") (pin "38") (pinfunction "LED_38_38") (pintype "passive"))
    )
    (net (code "129") (name "Net-(U1-LED_39)") (class "Default")
      (node (ref "R60") (pin "2") (pinfunction "2_2") (pintype "passive"))
      (node (ref "U1") (pin "39") (pinfunction "LED_39_39") (pintype "passive"))
    )
    (net (code "130") (name "Net-(U1-LED_40)") (class "Default")
      (node (ref "R58") (pin "2") (pinfunction "2_2") (pintype "passive"))
      (node (ref "U1") (pin "40") (pinfunction "LED_40_40") (pintype "passive"))
    )
    (net (code "131") (name "Net-(U1-LED_41)") (class "Default")
      (node (ref "R56") (pin "2") (pinfunction "2_2") (pintype "passive"))
      (node (ref "U1") (pin "41") (pinfunction "LED_41_41") (pintype "passive"))
    )
    (net (code "132") (name "Net-(U1-LED_42)") (class "Default")
      (node (ref "R54") (pin "2") (pinfunction "2_2") (pintype "passive"))
      (node (ref "U1") (pin "42") (pinfunction "LED_42_42") (pintype "passive"))
    )
    (net (code "133") (name "Net-(U1-LED_43)") (class "Default")
      (node (ref "R52") (pin "2") (pinfunction "2_2") (pintype "passive"))
      (node (ref "U1") (pin "43") (pinfunction "LED_43_43") (pintype "passive"))
    )
    (net (code "134") (name "Net-(U1-LED_44)") (class "Default")
      (node (ref "R50") (pin "2") (pinfunction "2_2") (pintype "passive"))
      (node (ref "U1") (pin "44") (pinfunction "LED_44_44") (pintype "passive"))
    )
    (net (code "135") (name "Net-(U1-LED_45)") (class "Default")
      (node (ref "R48") (pin "2") (pinfunction "2_2") (pintype "passive"))
      (node (ref "U1") (pin "45") (pinfunction "LED_45_45") (pintype "passive"))
    )
    (net (code "136") (name "Net-(U1-LED_46)") (class "Default")
      (node (ref "R46") (pin "2") (pinfunction "2_2") (pintype "passive"))
      (node (ref "U1") (pin "46") (pinfunction "LED_46_46") (pintype "passive"))
    )
    (net (code "137") (name "Net-(U1-LED_47)") (class "Default")
      (node (ref "R44") (pin "2") (pinfunction "2_2") (pintype "passive"))
      (node (ref "U1") (pin "47") (pinfunction "LED_47_47") (pintype "passive"))
    )
    (net (code "138") (name "Net-(U1-LED_48)") (class "Default")
      (node (ref "R42") (pin "2") (pinfunction "2_2") (pintype "passive"))
      (node (ref "U1") (pin "48") (pinfunction "LED_48_48") (pintype "passive"))
    )
    (net (code "139") (name "Net-(U1-LED_49)") (class "Default")
      (node (ref "R40") (pin "2") (pinfunction "2_2") (pintype "passive"))
      (node (ref "U1") (pin "49") (pinfunction "LED_49_49") (pintype "passive"))
    )
    (net (code "140") (name "Net-(U1-LED_50)") (class "Default")
      (node (ref "R38") (pin "2") (pinfunction "2_2") (pintype "passive"))
      (node (ref "U1") (pin "50") (pinfunction "LED_50_50") (pintype "passive"))
    )
    (net (code "141") (name "Net-(U1-LED_51)") (class "Default")
      (node (ref "R36") (pin "2") (pinfunction "2_2") (pintype "passive"))
      (node (ref "U1") (pin "51") (pinfunction "LED_51_51") (pintype "passive"))
    )
    (net (code "142") (name "Net-(U1-LED_52)") (class "Default")
      (node (ref "R34") (pin "2") (pinfunction "2_2") (pintype "passive"))
      (node (ref "U1") (pin "52") (pinfunction "LED_52_52") (pintype "passive"))
    )
    (net (code "143") (name "Net-(U1-LED_53)") (class "Default")
      (node (ref "R32") (pin "2") (pinfunction "2_2") (pintype "passive"))
      (node (ref "U1") (pin "53") (pinfunction "LED_53_53") (pintype "passive"))
    )
    (net (code "144") (name "Net-(U1-LED_54)") (class "Default")
      (node (ref "R30") (pin "2") (pinfunction "2_2") (pintype "passive"))
      (node (ref "U1") (pin "54") (pinfunction "LED_54_54") (pintype "passive"))
    )
    (net (code "145") (name "Net-(U1-LED_55)") (class "Default")
      (node (ref "R28") (pin "2") (pinfunction "2_2") (pintype "passive"))
      (node (ref "U1") (pin "55") (pinfunction "LED_55_55") (pintype "passive"))
    )
    (net (code "146") (name "Net-(U1-LED_56)") (class "Default")
      (node (ref "R26") (pin "2") (pinfunction "2_2") (pintype "passive"))
      (node (ref "U1") (pin "56") (pinfunction "LED_56_56") (pintype "passive"))
    )
    (net (code "147") (name "Net-(U1-LED_57)") (class "Default")
      (node (ref "R24") (pin "2") (pinfunction "2_2") (pintype "passive"))
      (node (ref "U1") (pin "57") (pinfunction "LED_57_57") (pintype "passive"))
    )
    (net (code "148") (name "Net-(U1-LED_58)") (class "Default")
      (node (ref "R22") (pin "2") (pinfunction "2_2") (pintype "passive"))
      (node (ref "U1") (pin "58") (pinfunction "LED_58_58") (pintype "passive"))
    )
    (net (code "149") (name "Net-(U1-LED_59)") (class "Default")
      (node (ref "R20") (pin "2") (pinfunction "2_2") (pintype "passive"))
      (node (ref "U1") (pin "59") (pinfunction "LED_59_59") (pintype "passive"))
    )
    (net (code "150") (name "Net-(U1-LED_60)") (class "Default")
      (node (ref "R18") (pin "2") (pinfunction "2_2") (pintype "passive"))
      (node (ref "U1") (pin "60") (pinfunction "LED_60_60") (pintype "passive"))
    )
    (net (code "151") (name "Net-(U1-LED_61)") (class "Default")
      (node (ref "R16") (pin "2") (pinfunction "2_2") (pintype "passive"))
      (node (ref "U1") (pin "61") (pinfunction "LED_61_61") (pintype "passive"))
    )
    (net (code "152") (name "Net-(U1-LED_62)") (class "Default")
      (node (ref "R14") (pin "2") (pinfunction "2_2") (pintype "passive"))
      (node (ref "U1") (pin "62") (pinfunction "LED_62_62") (pintype "passive"))
    )
    (net (code "153") (name "Net-(U1-LED_63)") (class "Default")
      (node (ref "R12") (pin "2") (pinfunction "2_2") (pintype "passive"))
      (node (ref "U1") (pin "63") (pinfunction "LED_63_63") (pintype "passive"))
    )
    (net (code "154") (name "Net-(U1-LED_64)") (class "Default")
      (node (ref "R10") (pin "2") (pinfunction "2_2") (pintype "passive"))
      (node (ref "U1") (pin "64") (pinfunction "LED_64_64") (pintype "passive"))
    )
  )
)
